# USBserial.net
KiCad netlist of a schematic drawn in Altium Designer
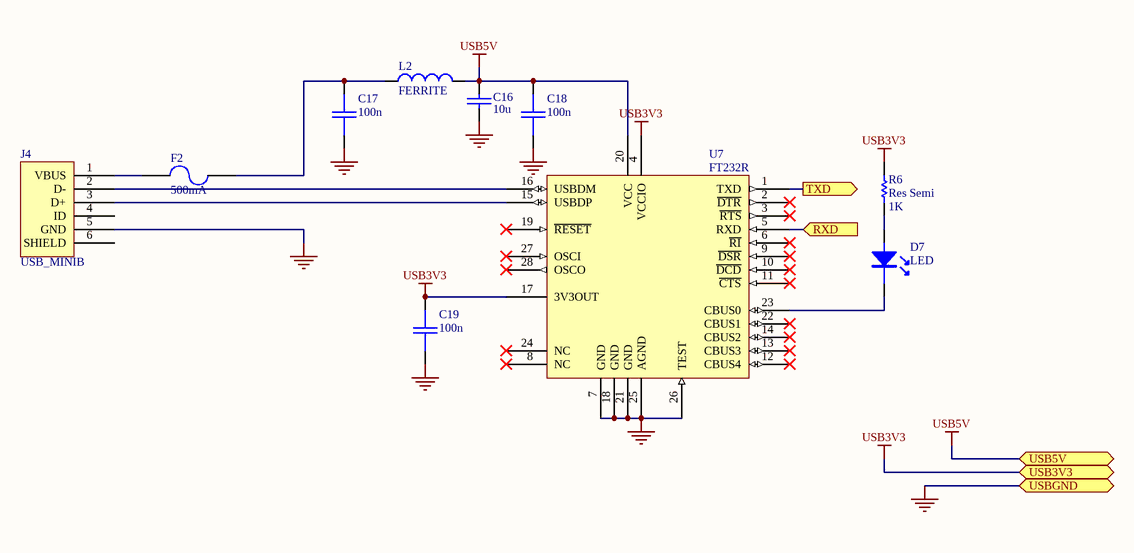
[diagram p0: USBserial.SchDoc]

(export (version "E")
  (design (tool "Eeschema 10.0.6"))
  (components
    (comp (ref "C16")
      (value "10u")
      (footprint "0805")
      (description "Capacitor")
      (libsource (lib "*") (part "CAP"))
    )
    (comp (ref "C17")
      (value "100n")
      (footprint "0603")
      (description "Capacitor")
      (libsource (lib "RCLDQ") (part "CAP"))
    )
    (comp (ref "C18")
      (value "100n")
      (footprint "0603")
      (description "Capacitor")
      (libsource (lib "RCLDQ") (part "CAP"))
    )
    (comp (ref "C19")
      (value "100n")
      (footprint "0603")
      (description "Capacitor")
      (libsource (lib "RCLDQ") (part "CAP"))
    )
    (comp (ref "D7") (value "LED") (footprint "3mmLED") (libsource (lib "RCLDQ") (part "LED")))
    (comp (ref "F2")
      (value "500mA")
      (footprint "LITTELFUSE-154")
      (description "Fuse")
      (libsource (lib "*") (part "FUSE2"))
    )
    (comp (ref "J4")
      (value "USB_MINIB")
      (footprint "USB_MINIB")
      (description "USB Mini B Connector")
      (libsource (lib "sion") (part "USB_miniB_SMT"))
    )
    (comp (ref "L2")
      (value "FERRITE")
      (footprint "0805")
      (description "Inductor")
      (fields (field (name "MANUFACTURER") "Generic Components"))
      (libsource (lib "RCLDQ") (part "INDUCTOR"))
    )
    (comp (ref "R6")
      (value "Res Semi")
      (footprint "1608[0603]")
      (description "Semiconductor Resistor")
      (fields (field (name "ALTIUM_VALUE") "1K"))
      (libsource (lib "Miscellaneous Devices") (part "Res Semi"))
    )
    (comp (ref "U7")
      (value "FT232R")
      (footprint "SSOP28")
      (description "USB UART IC")
      (libsource (lib "MiscellaneousIC") (part "FT232R"))
    )
  )
  (nets
    (net (code "1") (name "/RXD") (class "Default")
      (node (ref "U7") (pin "5") (pinfunction "RXD_5") (pintype "input"))
    )
    (net (code "2") (name "/TXD") (class "Default")
      (node (ref "U7") (pin "1") (pinfunction "TXD_1") (pintype "output"))
    )
    (net (code "3") (name "Net-(C17-Pad1)") (class "Default")
      (node (ref "C17") (pin "1") (pinfunction "1_1") (pintype "passive"))
      (node (ref "F2") (pin "2") (pinfunction "2_2") (pintype "passive"))
      (node (ref "L2") (pin "1") (pinfunction "1_1") (pintype "passive"))
    )
    (net (code "4") (name "Net-(D7-PadA)") (class "Default")
      (node (ref "D7") (pin "A") (pinfunction "A_A") (pintype "passive"))
      (node (ref "R6") (pin "1") (pinfunction "1_1") (pintype "passive"))
    )
    (net (code "5") (name "Net-(J4-D+)") (class "Default")
      (node (ref "J4") (pin "3") (pinfunction "D+_3") (pintype "passive"))
      (node (ref "U7") (pin "15") (pinfunction "USBDP_15") (pintype "bidirectional"))
    )
    (net (code "6") (name "Net-(J4-D-)") (class "Default")
      (node (ref "J4") (pin "2") (pinfunction "D-_2") (pintype "passive"))
      (node (ref "U7") (pin "16") (pinfunction "USBDM_16") (pintype "bidirectional"))
    )
    (net (code "7") (name "Net-(J4-VBUS)") (class "Default")
      (node (ref "F2") (pin "1") (pinfunction "1_1") (pintype "passive"))
      (node (ref "J4") (pin "1") (pinfunction "VBUS_1") (pintype "passive"))
    )
    (net (code "8") (name "Net-(U7-CBUS0)") (class "Default")
      (node (ref "D7") (pin "K") (pinfunction "K_K") (pintype "passive"))
      (node (ref "U7") (pin "23") (pinfunction "CBUS0_23") (pintype "bidirectional"))
    )
    (net (code "9") (name "USB3V3") (class "Default")
      (node (ref "C19") (pin "1") (pinfunction "1_1") (pintype "passive"))
      (node (ref "R6") (pin "2") (pinfunction "2_2") (pintype "passive"))
      (node (ref "U7") (pin "17") (pinfunction "3V3OUT_17") (pintype "power_in"))
      (node (ref "U7") (pin "4") (pinfunction "VCCIO_4") (pintype "power_in"))
    )
    (net (code "10") (name "USB5V") (class "Default")
      (node (ref "C16") (pin "2") (pinfunction "2_2") (pintype "passive"))
      (node (ref "C18") (pin "1") (pinfunction "1_1") (pintype "passive"))
      (node (ref "L2") (pin "2") (pinfunction "2_2") (pintype "passive"))
      (node (ref "U7") (pin "20") (pinfunction "VCC_20") (pintype "power_in"))
    )
    (net (code "11") (name "USBGND") (class "Default")
      (node (ref "C16") (pin "1") (pinfunction "1_1") (pintype "passive"))
      (node (ref "C17") (pin "2") (pinfunction "2_2") (pintype "passive"))
      (node (ref "C18") (pin "2") (pinfunction "2_2") (pintype "passive"))
      (node (ref "C19") (pin "2") (pinfunction "2_2") (pintype "passive"))
      (node (ref "J4") (pin "5") (pinfunction "GND_5") (pintype "passive"))
      (node (ref "U7") (pin "18") (pinfunction "GND_18") (pintype "power_in"))
      (node (ref "U7") (pin "21") (pinfunction "GND_21") (pintype "power_in"))
      (node (ref "U7") (pin "25") (pinfunction "AGND_25") (pintype "power_in"))
      (node (ref "U7") (pin "26") (pinfunction "TEST_26") (pintype "input"))
      (node (ref "U7") (pin "7") (pinfunction "GND_7") (pintype "power_in"))
    )
    (net (code "12") (name "unconnected-(J4-ID-Pad4)") (class "Default")
      (node (ref "J4") (pin "4") (pinfunction "ID_4") (pintype "passive"))
    )
    (net (code "13") (name "unconnected-(J4-SHIELD-Pad6)") (class "Default")
      (node (ref "J4") (pin "6") (pinfunction "SHIELD_6") (pintype "passive"))
    )
    (net (code "14") (name "unconnected-(U7-CBUS1-Pad22)") (class "Default")
      (node (ref "U7") (pin "22") (pinfunction "CBUS1_22") (pintype "bidirectional+no_connect"))
    )
    (net (code "15") (name "unconnected-(U7-CBUS2-Pad14)") (class "Default")
      (node (ref "U7") (pin "14") (pinfunction "CBUS2_14") (pintype "bidirectional+no_connect"))
    )
    (net (code "16") (name "unconnected-(U7-CBUS3-Pad13)") (class "Default")
      (node (ref "U7") (pin "13") (pinfunction "CBUS3_13") (pintype "bidirectional+no_connect"))
    )
    (net (code "17") (name "unconnected-(U7-CBUS4-Pad12)") (class "Default")
      (node (ref "U7") (pin "12") (pinfunction "CBUS4_12") (pintype "bidirectional+no_connect"))
    )
    (net (code "18") (name "unconnected-(U7-NC-Pad8)") (class "Default")
      (node (ref "U7") (pin "8") (pinfunction "NC_8") (pintype "passive+no_connect"))
    )
    (net (code "19") (name "unconnected-(U7-NC-Pad24)") (class "Default")
      (node (ref "U7") (pin "24") (pinfunction "NC_24") (pintype "passive+no_connect"))
    )
    (net (code "20") (name "unconnected-(U7-OSCI-Pad27)") (class "Default")
      (node (ref "U7") (pin "27") (pinfunction "OSCI_27") (pintype "input+no_connect"))
    )
    (net (code "21") (name "unconnected-(U7-OSCO-Pad28)") (class "Default")
      (node (ref "U7") (pin "28") (pinfunction "OSCO_28") (pintype "output+no_connect"))
    )
    (net (code "22") (name "unconnected-(U7-~{CTS}-Pad11)") (class "Default")
      (node (ref "U7") (pin "11") (pinfunction "~{CTS}_11") (pintype "input+no_connect"))
    )
    (net (code "23") (name "unconnected-(U7-~{DCD}-Pad10)") (class "Default")
      (node (ref "U7") (pin "10") (pinfunction "~{DCD}_10") (pintype "input+no_connect"))
    )
    (net (code "24") (name "unconnected-(U7-~{DSR}-Pad9)") (class "Default")
      (node (ref "U7") (pin "9") (pinfunction "~{DSR}_9") (pintype "input+no_connect"))
    )
    (net (code "25") (name "unconnected-(U7-~{DTR}-Pad2)") (class "Default")
      (node (ref "U7") (pin "2") (pinfunction "~{DTR}_2") (pintype "output+no_connect"))
    )
    (net (code "26") (name "unconnected-(U7-~{RESET}-Pad19)") (class "Default")
      (node (ref "U7") (pin "19") (pinfunction "~{RESET}_19") (pintype "input+no_connect"))
    )
    (net (code "27") (name "unconnected-(U7-~{RI}-Pad6)") (class "Default")
      (node (ref "U7") (pin "6") (pinfunction "~{RI}_6") (pintype "input+no_connect"))
    )
    (net (code "28") (name "unconnected-(U7-~{RTS}-Pad3)") (class "Default")
      (node (ref "U7") (pin "3") (pinfunction "~{RTS}_3") (pintype "output+no_connect"))
    )
  )
)
